# Mini58FDE_nRF24L01_Master.net
KiCad netlist of a schematic drawn in Altium Designer
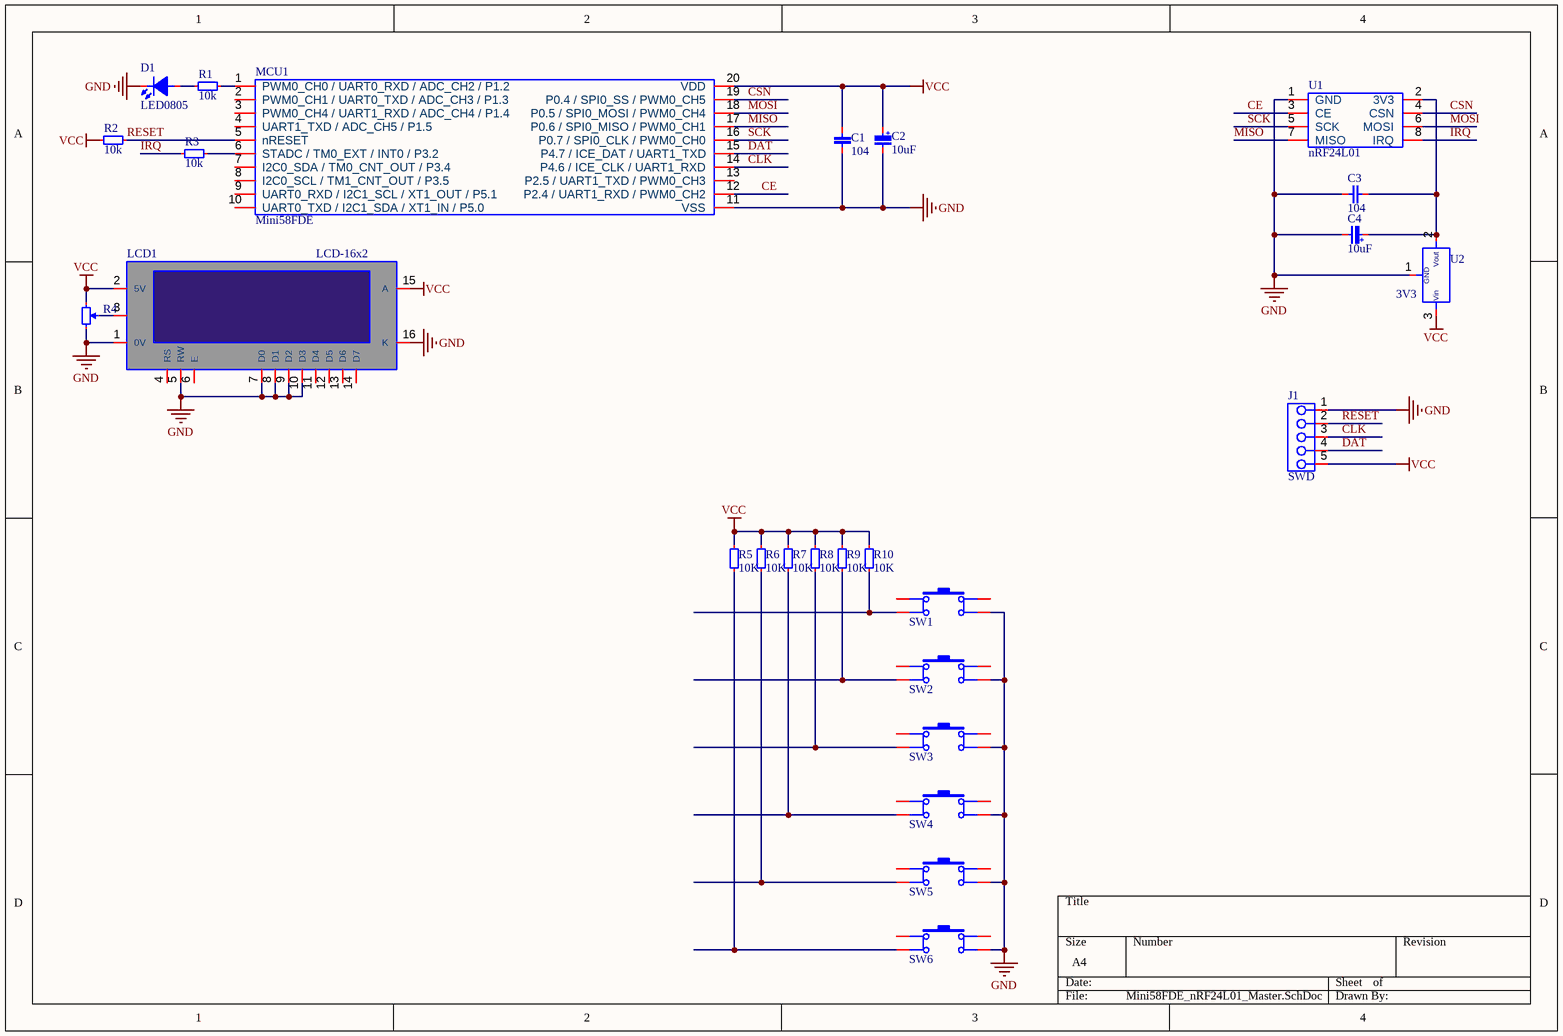
[diagram p0: Mini58FDE_nRF24L01_Master.SchDoc]

(export (version "E")
  (design (tool "Eeschema 10.0.6"))
  (components
    (comp (ref "C1") (value "104") (footprint "C0805") (libsource (lib "") (part "Capacitors(SMD)_1")))
    (comp (ref "C2")
      (value "10uF")
      (footprint "CAP_RAD_D05x11")
      (libsource (lib "MyAltiumLibrary") (part "Capacitor(Radian)"))
    )
    (comp (ref "C3")
      (value "104")
      (footprint "C1206")
      (libsource (lib "MyAltiumLibrary") (part "Capacitors(SMD)"))
    )
    (comp (ref "C4")
      (value "10uF")
      (footprint "CAP_RAD_D05x11")
      (libsource (lib "") (part "Capacitor(Radian)_1"))
    )
    (comp (ref "D1")
      (value "LED0805")
      (footprint "L0805RED")
      (libsource (lib "MyAltiumLibrary") (part "LED0805"))
    )
    (comp (ref "J1")
      (value "SWD")
      (footprint "HEADER-MALE-05PINS-2.54MM")
      (libsource (lib "MyAltiumLibrary") (part "HEADER-MALE-05PINS-2.54MM"))
    )
    (comp (ref "LCD1")
      (value "LCD-16x2")
      (footprint "LCD-16x2-VIOLET")
      (libsource (lib "MyAltiumLibrary") (part "LCD-16x2-Violet"))
    )
    (comp (ref "MCU1")
      (value "Mini58FDE")
      (footprint "TSSOP20_0.65_4.4")
      (description "Novoton 4Kb-RAM 32Kb-Flash")
      (libsource (lib "MyAltiumLibrary") (part "Mcu-Mini58FDE"))
    )
    (comp (ref "R1")
      (value "10k")
      (footprint "R0805")
      (libsource (lib "MyAltiumLibrary") (part "Resistors-SMD"))
    )
    (comp (ref "R2") (value "10k") (footprint "R0805") (libsource (lib "") (part "Resistors-SMD_1")))
    (comp (ref "R3")
      (value "10k")
      (footprint "R0805")
      (libsource (lib "MyAltiumLibrary") (part "Resistors-SMD"))
    )
    (comp (ref "R4")
      (value "Trimpot")
      (footprint "Trimpot 3296W")
      (libsource (lib "MyAltiumLibrary") (part "ResTrimpot"))
    )
    (comp (ref "R5")
      (value "10K")
      (footprint "RES-0.25W-H")
      (libsource (lib "MyAltiumLibrary") (part "Resistors THD"))
    )
    (comp (ref "R6")
      (value "10K")
      (footprint "RES-0.25W-H")
      (libsource (lib "MyAltiumLibrary") (part "Resistors THD"))
    )
    (comp (ref "R7")
      (value "10K")
      (footprint "RES-0.25W-H")
      (libsource (lib "MyAltiumLibrary") (part "Resistors THD"))
    )
    (comp (ref "R8")
      (value "10K")
      (footprint "RES-0.25W-H")
      (libsource (lib "MyAltiumLibrary") (part "Resistors THD"))
    )
    (comp (ref "R9")
      (value "10K")
      (footprint "RES-0.25W-H")
      (libsource (lib "MyAltiumLibrary") (part "Resistors THD"))
    )
    (comp (ref "R10")
      (value "10K")
      (footprint "RES-0.25W-H")
      (libsource (lib "MyAltiumLibrary") (part "Resistors THD"))
    )
    (comp (ref "SW1")
      (value "Button Hole")
      (footprint "BUTTON_HOLE_4.3mm")
      (libsource (lib "MyAltiumLibrary") (part "Button Hole"))
    )
    (comp (ref "SW2")
      (value "Button Hole")
      (footprint "BUTTON_HOLE_4.3mm")
      (libsource (lib "MyAltiumLibrary") (part "Button Hole"))
    )
    (comp (ref "SW3")
      (value "Button Hole")
      (footprint "BUTTON_HOLE_4.3mm")
      (libsource (lib "MyAltiumLibrary") (part "Button Hole"))
    )
    (comp (ref "SW4")
      (value "Button Hole")
      (footprint "BUTTON_HOLE_4.3mm")
      (libsource (lib "MyAltiumLibrary") (part "Button Hole"))
    )
    (comp (ref "SW5")
      (value "Button Hole")
      (footprint "BUTTON_HOLE_4.3mm")
      (libsource (lib "MyAltiumLibrary") (part "Button Hole"))
    )
    (comp (ref "SW6")
      (value "Button Hole")
      (footprint "BUTTON_HOLE_4.3mm")
      (libsource (lib "MyAltiumLibrary") (part "Button Hole"))
    )
    (comp (ref "U1")
      (value "nRF24L01")
      (footprint "nRF24L01")
      (libsource (lib "MyAltiumLibrary") (part "Module-nRF24L01"))
    )
    (comp (ref "U2")
      (value "3V3")
      (footprint "SOT223-3")
      (libsource (lib "MyAltiumLibrary") (part "Ic-AMS1117(SOT-223)"))
    )
  )
  (nets
    (net (code "1") (name "/CE") (class "Default")
      (node (ref "MCU1") (pin "12") (pinfunction "P2.4_/_UART1_RXD_/_PWM0_CH2_12") (pintype "passive"))
      (node (ref "U1") (pin "3") (pinfunction "CE_3") (pintype "passive"))
    )
    (net (code "2") (name "/CLK") (class "Default")
      (node (ref "J1") (pin "3") (pinfunction "3_3") (pintype "passive"))
      (node (ref "MCU1") (pin "14") (pinfunction "P4.6_/_ICE_CLK_/_UART1_RXD_14") (pintype "passive"))
    )
    (net (code "3") (name "/CSN") (class "Default")
      (node (ref "MCU1") (pin "19") (pinfunction "P0.4_/_SPI0_SS_/_PWM0_CH5_19") (pintype "passive"))
      (node (ref "U1") (pin "4") (pinfunction "CSN_4") (pintype "passive"))
    )
    (net (code "4") (name "/DAT") (class "Default")
      (node (ref "J1") (pin "4") (pinfunction "4_4") (pintype "passive"))
      (node (ref "MCU1") (pin "15") (pinfunction "P4.7_/_ICE_DAT_/_UART1_TXD_15") (pintype "passive"))
    )
    (net (code "5") (name "/IRQ") (class "Default")
      (node (ref "R3") (pin "1") (pinfunction "1_1") (pintype "passive"))
      (node (ref "U1") (pin "8") (pinfunction "IRQ_8") (pintype "passive"))
    )
    (net (code "6") (name "/MISO") (class "Default")
      (node (ref "MCU1") (pin "17") (pinfunction "P0.6_/_SPI0_MISO_/_PWM0_CH1_17") (pintype "passive"))
      (node (ref "U1") (pin "7") (pinfunction "MISO_7") (pintype "passive"))
    )
    (net (code "7") (name "/MOSI") (class "Default")
      (node (ref "MCU1") (pin "18") (pinfunction "P0.5_/_SPI0_MOSI_/_PWM0_CH4_18") (pintype "passive"))
      (node (ref "U1") (pin "6") (pinfunction "MOSI_6") (pintype "passive"))
    )
    (net (code "8") (name "/RESET") (class "Default")
      (node (ref "J1") (pin "2") (pinfunction "2_2") (pintype "passive"))
      (node (ref "MCU1") (pin "5") (pinfunction "nRESET_5") (pintype "passive"))
      (node (ref "R2") (pin "1") (pinfunction "1_1") (pintype "passive"))
    )
    (net (code "9") (name "/SCK") (class "Default")
      (node (ref "MCU1") (pin "16") (pinfunction "P0.7_/_SPI0_CLK_/_PWM0_CH0_16") (pintype "passive"))
      (node (ref "U1") (pin "5") (pinfunction "SCK_5") (pintype "passive"))
    )
    (net (code "10") (name "GND") (class "Default")
      (node (ref "C1") (pin "1") (pinfunction "1_1") (pintype "passive"))
      (node (ref "C2") (pin "2") (pinfunction "2_2") (pintype "passive"))
      (node (ref "C3") (pin "1") (pinfunction "1_1") (pintype "passive"))
      (node (ref "C4") (pin "2") (pinfunction "2_2") (pintype "passive"))
      (node (ref "D1") (pin "2") (pinfunction "K_2") (pintype "passive"))
      (node (ref "J1") (pin "1") (pinfunction "1_1") (pintype "passive"))
      (node (ref "LCD1") (pin "1") (pinfunction "0V_1") (pintype "passive"))
      (node (ref "LCD1") (pin "10") (pinfunction "D3_10") (pintype "passive"))
      (node (ref "LCD1") (pin "16") (pinfunction "K_16") (pintype "passive"))
      (node (ref "LCD1") (pin "5") (pinfunction "RW_5") (pintype "passive"))
      (node (ref "LCD1") (pin "7") (pinfunction "D0_7") (pintype "passive"))
      (node (ref "LCD1") (pin "8") (pinfunction "D1_8") (pintype "passive"))
      (node (ref "LCD1") (pin "9") (pinfunction "D2_9") (pintype "passive"))
      (node (ref "MCU1") (pin "11") (pinfunction "VSS_11") (pintype "passive"))
      (node (ref "R4") (pin "3") (pinfunction "-_3") (pintype "passive"))
      (node (ref "SW1") (pin "4") (pinfunction "4_4") (pintype "passive"))
      (node (ref "SW2") (pin "4") (pinfunction "4_4") (pintype "passive"))
      (node (ref "SW3") (pin "4") (pinfunction "4_4") (pintype "passive"))
      (node (ref "SW4") (pin "4") (pinfunction "4_4") (pintype "passive"))
      (node (ref "SW5") (pin "4") (pinfunction "4_4") (pintype "passive"))
      (node (ref "SW6") (pin "4") (pinfunction "4_4") (pintype "passive"))
      (node (ref "U1") (pin "1") (pinfunction "GND_1") (pintype "passive"))
      (node (ref "U2") (pin "1") (pinfunction "1_1") (pintype "passive"))
    )
    (net (code "11") (name "Net-(D1-A)") (class "Default")
      (node (ref "D1") (pin "1") (pinfunction "A_1") (pintype "passive"))
      (node (ref "R1") (pin "1") (pinfunction "1_1") (pintype "passive"))
    )
    (net (code "12") (name "Net-(LCD1-VEE)") (class "Default")
      (node (ref "LCD1") (pin "3") (pinfunction "VEE_3") (pintype "passive"))
      (node (ref "R4") (pin "2") (pinfunction "W_2") (pintype "passive"))
    )
    (net (code "13") (name "Net-(MCU1-PWM0_CH0_{slash}_UART0_RXD_{slash}_ADC_CH2_{slash}_P1.2)") (class "Default")
      (node (ref "MCU1") (pin "1") (pinfunction "PWM0_CH0_/_UART0_RXD_/_ADC_CH2_/_P1.2_1") (pintype "passive"))
      (node (ref "R1") (pin "2") (pinfunction "2_2") (pintype "passive"))
    )
    (net (code "14") (name "Net-(MCU1-STADC_{slash}_TM0_EXT_{slash}_INT0_{slash}_P3.2)") (class "Default")
      (node (ref "MCU1") (pin "6") (pinfunction "STADC_/_TM0_EXT_/_INT0_/_P3.2_6") (pintype "passive"))
      (node (ref "R3") (pin "2") (pinfunction "2_2") (pintype "passive"))
    )
    (net (code "15") (name "Net-(R5-Pad1)") (class "Default")
      (node (ref "R5") (pin "1") (pinfunction "1_1") (pintype "passive"))
      (node (ref "SW6") (pin "2") (pinfunction "2_2") (pintype "passive"))
    )
    (net (code "16") (name "Net-(R6-Pad1)") (class "Default")
      (node (ref "R6") (pin "1") (pinfunction "1_1") (pintype "passive"))
      (node (ref "SW5") (pin "2") (pinfunction "2_2") (pintype "passive"))
    )
    (net (code "17") (name "Net-(R7-Pad1)") (class "Default")
      (node (ref "R7") (pin "1") (pinfunction "1_1") (pintype "passive"))
      (node (ref "SW4") (pin "2") (pinfunction "2_2") (pintype "passive"))
    )
    (net (code "18") (name "Net-(R8-Pad1)") (class "Default")
      (node (ref "R8") (pin "1") (pinfunction "1_1") (pintype "passive"))
      (node (ref "SW3") (pin "2") (pinfunction "2_2") (pintype "passive"))
    )
    (net (code "19") (name "Net-(R9-Pad1)") (class "Default")
      (node (ref "R9") (pin "1") (pinfunction "1_1") (pintype "passive"))
      (node (ref "SW2") (pin "2") (pinfunction "2_2") (pintype "passive"))
    )
    (net (code "20") (name "Net-(R10-Pad1)") (class "Default")
      (node (ref "R10") (pin "1") (pinfunction "1_1") (pintype "passive"))
      (node (ref "SW1") (pin "2") (pinfunction "2_2") (pintype "passive"))
    )
    (net (code "21") (name "Net-(U1-3V3)") (class "Default")
      (node (ref "C3") (pin "2") (pinfunction "2_2") (pintype "passive"))
      (node (ref "C4") (pin "1") (pinfunction "1_1") (pintype "passive"))
      (node (ref "U1") (pin "2") (pinfunction "3V3_2") (pintype "passive"))
      (node (ref "U2") (pin "2") (pinfunction "2_2") (pintype "passive"))
    )
    (net (code "22") (name "VCC") (class "Default")
      (node (ref "C1") (pin "2") (pinfunction "2_2") (pintype "passive"))
      (node (ref "C2") (pin "1") (pinfunction "1_1") (pintype "passive"))
      (node (ref "J1") (pin "5") (pinfunction "5_5") (pintype "passive"))
      (node (ref "LCD1") (pin "15") (pinfunction "A_15") (pintype "passive"))
      (node (ref "LCD1") (pin "2") (pinfunction "5V_2") (pintype "passive"))
      (node (ref "MCU1") (pin "20") (pinfunction "VDD_20") (pintype "passive"))
      (node (ref "R10") (pin "2") (pinfunction "2_2") (pintype "passive"))
      (node (ref "R2") (pin "2") (pinfunction "2_2") (pintype "passive"))
      (node (ref "R4") (pin "1") (pinfunction "+_1") (pintype "passive"))
      (node (ref "R5") (pin "2") (pinfunction "2_2") (pintype "passive"))
      (node (ref "R6") (pin "2") (pinfunction "2_2") (pintype "passive"))
      (node (ref "R7") (pin "2") (pinfunction "2_2") (pintype "passive"))
      (node (ref "R8") (pin "2") (pinfunction "2_2") (pintype "passive"))
      (node (ref "R9") (pin "2") (pinfunction "2_2") (pintype "passive"))
      (node (ref "U2") (pin "3") (pinfunction "3_3") (pintype "passive"))
    )
    (net (code "23") (name "unconnected-(LCD1-D4-Pad11)") (class "Default")
      (node (ref "LCD1") (pin "11") (pinfunction "D4_11") (pintype "passive"))
    )
    (net (code "24") (name "unconnected-(LCD1-D5-Pad12)") (class "Default")
      (node (ref "LCD1") (pin "12") (pinfunction "D5_12") (pintype "passive"))
    )
    (net (code "25") (name "unconnected-(LCD1-D6-Pad13)") (class "Default")
      (node (ref "LCD1") (pin "13") (pinfunction "D6_13") (pintype "passive"))
    )
    (net (code "26") (name "unconnected-(LCD1-D7-Pad14)") (class "Default")
      (node (ref "LCD1") (pin "14") (pinfunction "D7_14") (pintype "passive"))
    )
    (net (code "27") (name "unconnected-(LCD1-E-Pad6)") (class "Default")
      (node (ref "LCD1") (pin "6") (pinfunction "E_6") (pintype "passive"))
    )
    (net (code "28") (name "unconnected-(LCD1-RS-Pad4)") (class "Default")
      (node (ref "LCD1") (pin "4") (pinfunction "RS_4") (pintype "passive"))
    )
    (net (code "29") (name "unconnected-(MCU1-I2C0_SCL_{slash}_TM1_CNT_OUT_{slash}_P3.5-Pad8)") (class "Default")
      (node (ref "MCU1") (pin "8") (pinfunction "I2C0_SCL_/_TM1_CNT_OUT_/_P3.5_8") (pintype "passive"))
    )
    (net (code "30") (name "unconnected-(MCU1-I2C0_SDA_{slash}_TM0_CNT_OUT_{slash}_P3.4-Pad7)") (class "Default")
      (node (ref "MCU1") (pin "7") (pinfunction "I2C0_SDA_/_TM0_CNT_OUT_/_P3.4_7") (pintype "passive"))
    )
    (net (code "31") (name "unconnected-(MCU1-P2.5_{slash}_UART1_TXD_{slash}_PWM0_CH3-Pad13)") (class "Default")
      (node (ref "MCU1") (pin "13") (pinfunction "P2.5_/_UART1_TXD_/_PWM0_CH3_13") (pintype "passive"))
    )
    (net (code "32") (name "unconnected-(MCU1-PWM0_CH1_{slash}_UART0_TXD_{slash}_ADC_CH3_{slash}_P1.3-Pad2)") (class "Default")
      (node (ref "MCU1") (pin "2") (pinfunction "PWM0_CH1_/_UART0_TXD_/_ADC_CH3_/_P1.3_2") (pintype "passive"))
    )
    (net (code "33") (name "unconnected-(MCU1-PWM0_CH4_{slash}_UART1_RXD_{slash}_ADC_CH4_{slash}_P1.4-Pad3)") (class "Default")
      (node (ref "MCU1") (pin "3") (pinfunction "PWM0_CH4_/_UART1_RXD_/_ADC_CH4_/_P1.4_3") (pintype "passive"))
    )
    (net (code "34") (name "unconnected-(MCU1-UART0_RXD_{slash}_I2C1_SCL_{slash}_XT1_OUT_{slash}_P5.1-Pad9)") (class "Default")
      (node (ref "MCU1") (pin "9") (pinfunction "UART0_RXD_/_I2C1_SCL_/_XT1_OUT_/_P5.1_9") (pintype "passive"))
    )
    (net (code "35") (name "unconnected-(MCU1-UART0_TXD_{slash}_I2C1_SDA_{slash}_XT1_IN_{slash}_P5.0-Pad10)") (class "Default")
      (node (ref "MCU1") (pin "10") (pinfunction "UART0_TXD_/_I2C1_SDA_/_XT1_IN_/_P5.0_10") (pintype "passive"))
    )
    (net (code "36") (name "unconnected-(MCU1-UART1_TXD_{slash}_ADC_CH5_{slash}_P1.5-Pad4)") (class "Default")
      (node (ref "MCU1") (pin "4") (pinfunction "UART1_TXD_/_ADC_CH5_/_P1.5_4") (pintype "passive"))
    )
    (net (code "37") (name "unconnected-(SW1-Pad1)") (class "Default")
      (node (ref "SW1") (pin "1") (pinfunction "1_1") (pintype "passive"))
    )
    (net (code "38") (name "unconnected-(SW1-Pad3)") (class "Default")
      (node (ref "SW1") (pin "3") (pinfunction "3_3") (pintype "passive"))
    )
    (net (code "39") (name "unconnected-(SW2-Pad1)") (class "Default")
      (node (ref "SW2") (pin "1") (pinfunction "1_1") (pintype "passive"))
    )
    (net (code "40") (name "unconnected-(SW2-Pad3)") (class "Default")
      (node (ref "SW2") (pin "3") (pinfunction "3_3") (pintype "passive"))
    )
    (net (code "41") (name "unconnected-(SW3-Pad1)") (class "Default")
      (node (ref "SW3") (pin "1") (pinfunction "1_1") (pintype "passive"))
    )
    (net (code "42") (name "unconnected-(SW3-Pad3)") (class "Default")
      (node (ref "SW3") (pin "3") (pinfunction "3_3") (pintype "passive"))
    )
    (net (code "43") (name "unconnected-(SW4-Pad1)") (class "Default")
      (node (ref "SW4") (pin "1") (pinfunction "1_1") (pintype "passive"))
    )
    (net (code "44") (name "unconnected-(SW4-Pad3)") (class "Default")
      (node (ref "SW4") (pin "3") (pinfunction "3_3") (pintype "passive"))
    )
    (net (code "45") (name "unconnected-(SW5-Pad1)") (class "Default")
      (node (ref "SW5") (pin "1") (pinfunction "1_1") (pintype "passive"))
    )
    (net (code "46") (name "unconnected-(SW5-Pad3)") (class "Default")
      (node (ref "SW5") (pin "3") (pinfunction "3_3") (pintype "passive"))
    )
    (net (code "47") (name "unconnected-(SW6-Pad1)") (class "Default")
      (node (ref "SW6") (pin "1") (pinfunction "1_1") (pintype "passive"))
    )
    (net (code "48") (name "unconnected-(SW6-Pad3)") (class "Default")
      (node (ref "SW6") (pin "3") (pinfunction "3_3") (pintype "passive"))
    )
  )
)
